# bala.net
KiCad netlist of a schematic drawn in Altium Designer
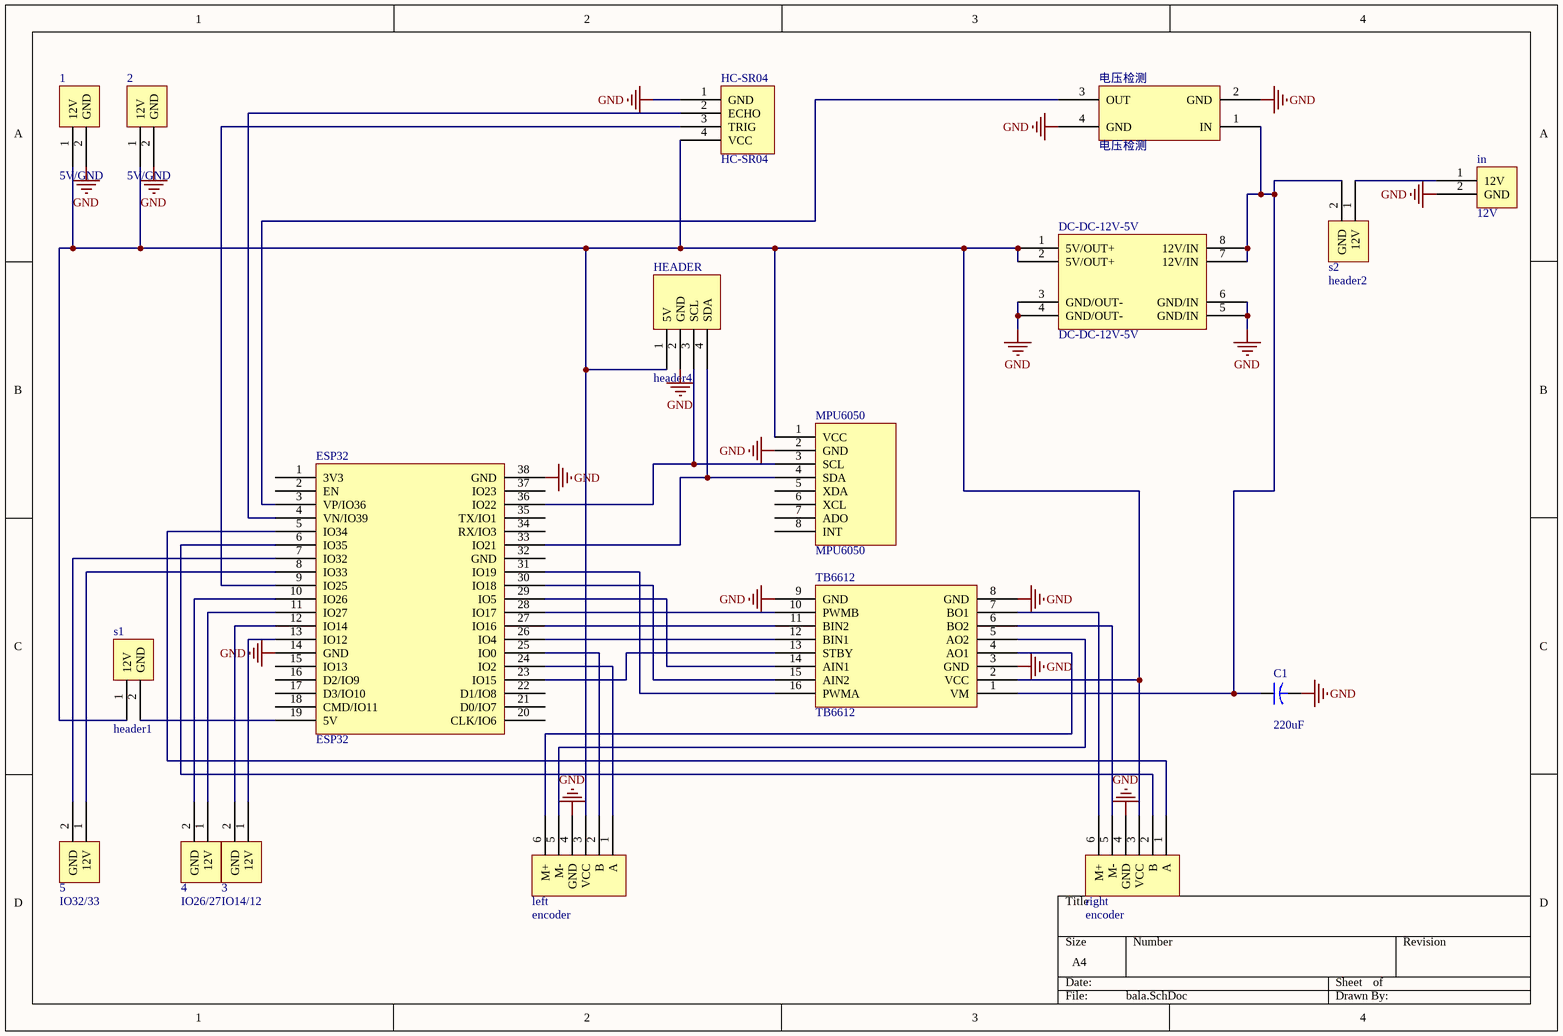
[diagram p0: bala.SchDoc]

(export (version "E")
  (design (tool "Eeschema 10.0.6"))
  (components
    (comp (ref "1")
      (value "5V/GND")
      (footprint "PCBComponent_1")
      (libsource (lib "12V") (part "Component_1"))
    )
    (comp (ref "2")
      (value "5V/GND")
      (footprint "PCBComponent_1")
      (libsource (lib "12V") (part "Component_1"))
    )
    (comp (ref "3")
      (value "IO14/12")
      (footprint "PCBComponent_1")
      (libsource (lib "") (part "Component_1_1"))
    )
    (comp (ref "4")
      (value "IO26/27")
      (footprint "PCBComponent_1")
      (libsource (lib "") (part "Component_1_1"))
    )
    (comp (ref "5")
      (value "IO32/33")
      (footprint "PCBComponent_1")
      (libsource (lib "") (part "Component_1_1"))
    )
    (comp (ref "C1")
      (value "220uF")
      (footprint "CAPR5-4X5")
      (description "Capacitor")
      (fields (field (name "PUBLISHER") "Altium Limited"))
      (libsource (lib "Miscellaneous Devices") (part "Cap2"))
    )
    (comp (ref "DC-DC-12V-5V")
      (value "DC-DC-12V-5V")
      (footprint "PCBComponent_1")
      (libsource (lib "DC-DC-12V-5V") (part "Component_1"))
    )
    (comp (ref "ESP32")
      (value "ESP32")
      (footprint "MPU6050")
      (libsource (lib "ESP32-DEVKIT") (part "Component_1"))
    )
    (comp (ref "HC-SR04")
      (value "HC-SR04")
      (footprint "PCBComponent_1")
      (libsource (lib "HC-SR04") (part "Component_1"))
    )
    (comp (ref "HEADER")
      (value "header4")
      (footprint "PCBComponent_1")
      (libsource (lib "header4") (part "Component_1"))
    )
    (comp (ref "in") (value "12V") (footprint "PCBComponent_1") (libsource (lib "") (part "Component_1_2")))
    (comp (ref "left")
      (value "encoder")
      (footprint "PCBComponent_1")
      (libsource (lib "编码器接口") (part "Component_1"))
    )
    (comp (ref "MPU6050")
      (value "MPU6050")
      (footprint "PCBComponent_1")
      (libsource (lib "MPU6050") (part "Component_1"))
    )
    (comp (ref "right")
      (value "encoder")
      (footprint "PCBComponent_1")
      (libsource (lib "编码器接口") (part "Component_1"))
    )
    (comp (ref "s1")
      (value "header1")
      (footprint "PCBComponent_1")
      (libsource (lib "12V") (part "Component_1"))
    )
    (comp (ref "s2")
      (value "header2")
      (footprint "PCBComponent_1")
      (libsource (lib "") (part "Component_1_1"))
    )
    (comp (ref "TB6612")
      (value "TB6612")
      (footprint "PCBComponent_1")
      (libsource (lib "TB6612") (part "Component_1"))
    )
    (comp (ref "电压检测")
      (value "电压检测")
      (footprint "PCBComponent_1")
      (libsource (lib "电压检测") (part "Component_1"))
    )
  )
  (nets
    (net (code "1") (name "GND") (class "Default")
      (node (ref "1") (pin "2") (pinfunction "GND_2") (pintype "passive"))
      (node (ref "2") (pin "2") (pinfunction "GND_2") (pintype "passive"))
      (node (ref "C1") (pin "2") (pinfunction "2_2") (pintype "passive"))
      (node (ref "DC-DC-12V-5V") (pin "3") (pinfunction "GND/OUT-_3") (pintype "passive"))
      (node (ref "DC-DC-12V-5V") (pin "4") (pinfunction "GND/OUT-_4") (pintype "passive"))
      (node (ref "DC-DC-12V-5V") (pin "5") (pinfunction "GND/IN_5") (pintype "passive"))
      (node (ref "DC-DC-12V-5V") (pin "6") (pinfunction "GND/IN_6") (pintype "passive"))
      (node (ref "ESP32") (pin "14") (pinfunction "GND_14") (pintype "passive"))
      (node (ref "ESP32") (pin "38") (pinfunction "GND_38") (pintype "passive"))
      (node (ref "HC-SR04") (pin "1") (pinfunction "GND_1") (pintype "passive"))
      (node (ref "HEADER") (pin "2") (pinfunction "GND_2") (pintype "passive"))
      (node (ref "MPU6050") (pin "2") (pinfunction "GND_2") (pintype "passive"))
      (node (ref "TB6612") (pin "3") (pinfunction "GND_3") (pintype "passive"))
      (node (ref "TB6612") (pin "8") (pinfunction "GND_8") (pintype "passive"))
      (node (ref "TB6612") (pin "9") (pinfunction "GND_9") (pintype "passive"))
      (node (ref "in") (pin "2") (pinfunction "GND_2") (pintype "passive"))
      (node (ref "left") (pin "4") (pinfunction "GND_4") (pintype "passive"))
      (node (ref "right") (pin "4") (pinfunction "GND_4") (pintype "passive"))
      (node (ref "电压检测") (pin "2") (pinfunction "GND_2") (pintype "passive"))
      (node (ref "电压检测") (pin "4") (pinfunction "GND_4") (pintype "passive"))
    )
    (net (code "2") (name "Net-(1-12V)") (class "Default")
      (node (ref "1") (pin "1") (pinfunction "12V_1") (pintype "passive"))
      (node (ref "2") (pin "1") (pinfunction "12V_1") (pintype "passive"))
      (node (ref "DC-DC-12V-5V") (pin "1") (pinfunction "5V/OUT+_1") (pintype "passive"))
      (node (ref "DC-DC-12V-5V") (pin "2") (pinfunction "5V/OUT+_2") (pintype "passive"))
      (node (ref "HC-SR04") (pin "4") (pinfunction "VCC_4") (pintype "passive"))
      (node (ref "HEADER") (pin "1") (pinfunction "5V_1") (pintype "passive"))
      (node (ref "MPU6050") (pin "1") (pinfunction "VCC_1") (pintype "passive"))
      (node (ref "TB6612") (pin "2") (pinfunction "VCC_2") (pintype "passive"))
      (node (ref "left") (pin "3") (pinfunction "VCC_3") (pintype "passive"))
      (node (ref "right") (pin "3") (pinfunction "VCC_3") (pintype "passive"))
      (node (ref "s1") (pin "1") (pinfunction "12V_1") (pintype "passive"))
    )
    (net (code "3") (name "Net-(3-12V)") (class "Default")
      (node (ref "3") (pin "1") (pinfunction "12V_1") (pintype "passive"))
      (node (ref "ESP32") (pin "13") (pinfunction "IO12_13") (pintype "passive"))
    )
    (net (code "4") (name "Net-(3-GND)") (class "Default")
      (node (ref "3") (pin "2") (pinfunction "GND_2") (pintype "passive"))
      (node (ref "ESP32") (pin "12") (pinfunction "IO14_12") (pintype "passive"))
    )
    (net (code "5") (name "Net-(4-12V)") (class "Default")
      (node (ref "4") (pin "1") (pinfunction "12V_1") (pintype "passive"))
      (node (ref "ESP32") (pin "11") (pinfunction "IO27_11") (pintype "passive"))
    )
    (net (code "6") (name "Net-(4-GND)") (class "Default")
      (node (ref "4") (pin "2") (pinfunction "GND_2") (pintype "passive"))
      (node (ref "ESP32") (pin "10") (pinfunction "IO26_10") (pintype "passive"))
    )
    (net (code "7") (name "Net-(5-12V)") (class "Default")
      (node (ref "5") (pin "1") (pinfunction "12V_1") (pintype "passive"))
      (node (ref "ESP32") (pin "8") (pinfunction "IO33_8") (pintype "passive"))
    )
    (net (code "8") (name "Net-(5-GND)") (class "Default")
      (node (ref "5") (pin "2") (pinfunction "GND_2") (pintype "passive"))
      (node (ref "ESP32") (pin "7") (pinfunction "IO32_7") (pintype "passive"))
    )
    (net (code "9") (name "Net-(ESP32-5V)") (class "Default")
      (node (ref "ESP32") (pin "19") (pinfunction "5V_19") (pintype "passive"))
      (node (ref "s1") (pin "2") (pinfunction "GND_2") (pintype "passive"))
    )
    (net (code "10") (name "Net-(ESP32-IO0)") (class "Default")
      (node (ref "ESP32") (pin "25") (pinfunction "IO0_25") (pintype "passive"))
      (node (ref "left") (pin "2") (pinfunction "B_2") (pintype "passive"))
    )
    (net (code "11") (name "Net-(ESP32-IO2)") (class "Default")
      (node (ref "ESP32") (pin "24") (pinfunction "IO2_24") (pintype "passive"))
      (node (ref "left") (pin "1") (pinfunction "A_1") (pintype "passive"))
    )
    (net (code "12") (name "Net-(ESP32-IO4)") (class "Default")
      (node (ref "ESP32") (pin "26") (pinfunction "IO4_26") (pintype "passive"))
      (node (ref "TB6612") (pin "12") (pinfunction "BIN1_12") (pintype "passive"))
    )
    (net (code "13") (name "Net-(ESP32-IO5)") (class "Default")
      (node (ref "ESP32") (pin "29") (pinfunction "IO5_29") (pintype "passive"))
      (node (ref "TB6612") (pin "14") (pinfunction "AIN1_14") (pintype "passive"))
    )
    (net (code "14") (name "Net-(ESP32-IO15)") (class "Default")
      (node (ref "ESP32") (pin "23") (pinfunction "IO15_23") (pintype "passive"))
      (node (ref "TB6612") (pin "13") (pinfunction "STBY_13") (pintype "passive"))
    )
    (net (code "15") (name "Net-(ESP32-IO16)") (class "Default")
      (node (ref "ESP32") (pin "27") (pinfunction "IO16_27") (pintype "passive"))
      (node (ref "TB6612") (pin "11") (pinfunction "BIN2_11") (pintype "passive"))
    )
    (net (code "16") (name "Net-(ESP32-IO17)") (class "Default")
      (node (ref "ESP32") (pin "28") (pinfunction "IO17_28") (pintype "passive"))
      (node (ref "TB6612") (pin "10") (pinfunction "PWMB_10") (pintype "passive"))
    )
    (net (code "17") (name "Net-(ESP32-IO18)") (class "Default")
      (node (ref "ESP32") (pin "30") (pinfunction "IO18_30") (pintype "passive"))
      (node (ref "TB6612") (pin "15") (pinfunction "AIN2_15") (pintype "passive"))
    )
    (net (code "18") (name "Net-(ESP32-IO19)") (class "Default")
      (node (ref "ESP32") (pin "31") (pinfunction "IO19_31") (pintype "passive"))
      (node (ref "TB6612") (pin "16") (pinfunction "PWMA_16") (pintype "passive"))
    )
    (net (code "19") (name "Net-(ESP32-IO21)") (class "Default")
      (node (ref "ESP32") (pin "33") (pinfunction "IO21_33") (pintype "passive"))
      (node (ref "HEADER") (pin "4") (pinfunction "SDA_4") (pintype "passive"))
      (node (ref "MPU6050") (pin "4") (pinfunction "SDA_4") (pintype "passive"))
    )
    (net (code "20") (name "Net-(ESP32-IO22)") (class "Default")
      (node (ref "ESP32") (pin "36") (pinfunction "IO22_36") (pintype "passive"))
      (node (ref "HEADER") (pin "3") (pinfunction "SCL_3") (pintype "passive"))
      (node (ref "MPU6050") (pin "3") (pinfunction "SCL_3") (pintype "passive"))
    )
    (net (code "21") (name "Net-(ESP32-IO25)") (class "Default")
      (node (ref "ESP32") (pin "9") (pinfunction "IO25_9") (pintype "passive"))
      (node (ref "HC-SR04") (pin "3") (pinfunction "TRIG_3") (pintype "passive"))
    )
    (net (code "22") (name "Net-(ESP32-IO34)") (class "Default")
      (node (ref "ESP32") (pin "5") (pinfunction "IO34_5") (pintype "passive"))
      (node (ref "right") (pin "1") (pinfunction "A_1") (pintype "passive"))
    )
    (net (code "23") (name "Net-(ESP32-IO35)") (class "Default")
      (node (ref "ESP32") (pin "6") (pinfunction "IO35_6") (pintype "passive"))
      (node (ref "right") (pin "2") (pinfunction "B_2") (pintype "passive"))
    )
    (net (code "24") (name "Net-(ESP32-VN{slash}IO39)") (class "Default")
      (node (ref "ESP32") (pin "4") (pinfunction "VN/IO39_4") (pintype "passive"))
      (node (ref "HC-SR04") (pin "2") (pinfunction "ECHO_2") (pintype "passive"))
    )
    (net (code "25") (name "Net-(ESP32-VP{slash}IO36)") (class "Default")
      (node (ref "ESP32") (pin "3") (pinfunction "VP/IO36_3") (pintype "passive"))
      (node (ref "电压检测") (pin "3") (pinfunction "OUT_3") (pintype "passive"))
    )
    (net (code "26") (name "Net-(TB6612-AO1)") (class "Default")
      (node (ref "TB6612") (pin "4") (pinfunction "AO1_4") (pintype "passive"))
      (node (ref "left") (pin "6") (pinfunction "M+_6") (pintype "passive"))
    )
    (net (code "27") (name "Net-(TB6612-AO2)") (class "Default")
      (node (ref "TB6612") (pin "5") (pinfunction "AO2_5") (pintype "passive"))
      (node (ref "left") (pin "5") (pinfunction "M-_5") (pintype "passive"))
    )
    (net (code "28") (name "Net-(TB6612-BO1)") (class "Default")
      (node (ref "TB6612") (pin "7") (pinfunction "BO1_7") (pintype "passive"))
      (node (ref "right") (pin "6") (pinfunction "M+_6") (pintype "passive"))
    )
    (net (code "29") (name "Net-(TB6612-BO2)") (class "Default")
      (node (ref "TB6612") (pin "6") (pinfunction "BO2_6") (pintype "passive"))
      (node (ref "right") (pin "5") (pinfunction "M-_5") (pintype "passive"))
    )
    (net (code "30") (name "Net-(TB6612-VM)") (class "Default")
      (node (ref "C1") (pin "1") (pinfunction "1_1") (pintype "passive"))
      (node (ref "DC-DC-12V-5V") (pin "7") (pinfunction "12V/IN_7") (pintype "passive"))
      (node (ref "DC-DC-12V-5V") (pin "8") (pinfunction "12V/IN_8") (pintype "passive"))
      (node (ref "TB6612") (pin "1") (pinfunction "VM_1") (pintype "passive"))
      (node (ref "s2") (pin "2") (pinfunction "GND_2") (pintype "passive"))
      (node (ref "电压检测") (pin "1") (pinfunction "IN_1") (pintype "passive"))
    )
    (net (code "31") (name "Net-(in-12V)") (class "Default")
      (node (ref "in") (pin "1") (pinfunction "12V_1") (pintype "passive"))
      (node (ref "s2") (pin "1") (pinfunction "12V_1") (pintype "passive"))
    )
    (net (code "32") (name "unconnected-(ESP32-3V3-Pad1)") (class "Default")
      (node (ref "ESP32") (pin "1") (pinfunction "3V3_1") (pintype "passive"))
    )
    (net (code "33") (name "unconnected-(ESP32-CLK{slash}IO6-Pad20)") (class "Default")
      (node (ref "ESP32") (pin "20") (pinfunction "CLK/IO6_20") (pintype "passive"))
    )
    (net (code "34") (name "unconnected-(ESP32-CMD{slash}IO11-Pad18)") (class "Default")
      (node (ref "ESP32") (pin "18") (pinfunction "CMD/IO11_18") (pintype "passive"))
    )
    (net (code "35") (name "unconnected-(ESP32-D0{slash}IO7-Pad21)") (class "Default")
      (node (ref "ESP32") (pin "21") (pinfunction "D0/IO7_21") (pintype "passive"))
    )
    (net (code "36") (name "unconnected-(ESP32-D1{slash}IO8-Pad22)") (class "Default")
      (node (ref "ESP32") (pin "22") (pinfunction "D1/IO8_22") (pintype "passive"))
    )
    (net (code "37") (name "unconnected-(ESP32-D2{slash}IO9-Pad16)") (class "Default")
      (node (ref "ESP32") (pin "16") (pinfunction "D2/IO9_16") (pintype "passive"))
    )
    (net (code "38") (name "unconnected-(ESP32-D3{slash}IO10-Pad17)") (class "Default")
      (node (ref "ESP32") (pin "17") (pinfunction "D3/IO10_17") (pintype "passive"))
    )
    (net (code "39") (name "unconnected-(ESP32-EN-Pad2)") (class "Default")
      (node (ref "ESP32") (pin "2") (pinfunction "EN_2") (pintype "passive"))
    )
    (net (code "40") (name "unconnected-(ESP32-GND-Pad32)") (class "Default")
      (node (ref "ESP32") (pin "32") (pinfunction "GND_32") (pintype "passive"))
    )
    (net (code "41") (name "unconnected-(ESP32-IO13-Pad15)") (class "Default")
      (node (ref "ESP32") (pin "15") (pinfunction "IO13_15") (pintype "passive"))
    )
    (net (code "42") (name "unconnected-(ESP32-IO23-Pad37)") (class "Default")
      (node (ref "ESP32") (pin "37") (pinfunction "IO23_37") (pintype "passive"))
    )
    (net (code "43") (name "unconnected-(ESP32-RX{slash}IO3-Pad34)") (class "Default")
      (node (ref "ESP32") (pin "34") (pinfunction "RX/IO3_34") (pintype "passive"))
    )
    (net (code "44") (name "unconnected-(ESP32-TX{slash}IO1-Pad35)") (class "Default")
      (node (ref "ESP32") (pin "35") (pinfunction "TX/IO1_35") (pintype "passive"))
    )
    (net (code "45") (name "unconnected-(MPU6050-ADO-Pad7)") (class "Default")
      (node (ref "MPU6050") (pin "7") (pinfunction "ADO_7") (pintype "passive"))
    )
    (net (code "46") (name "unconnected-(MPU6050-INT-Pad8)") (class "Default")
      (node (ref "MPU6050") (pin "8") (pinfunction "INT_8") (pintype "passive"))
    )
    (net (code "47") (name "unconnected-(MPU6050-XCL-Pad6)") (class "Default")
      (node (ref "MPU6050") (pin "6") (pinfunction "XCL_6") (pintype "passive"))
    )
    (net (code "48") (name "unconnected-(MPU6050-XDA-Pad5)") (class "Default")
      (node (ref "MPU6050") (pin "5") (pinfunction "XDA_5") (pintype "passive"))
    )
  )
)
